# EEPROM_FLASH.net
KiCad netlist of a schematic drawn in Altium Designer
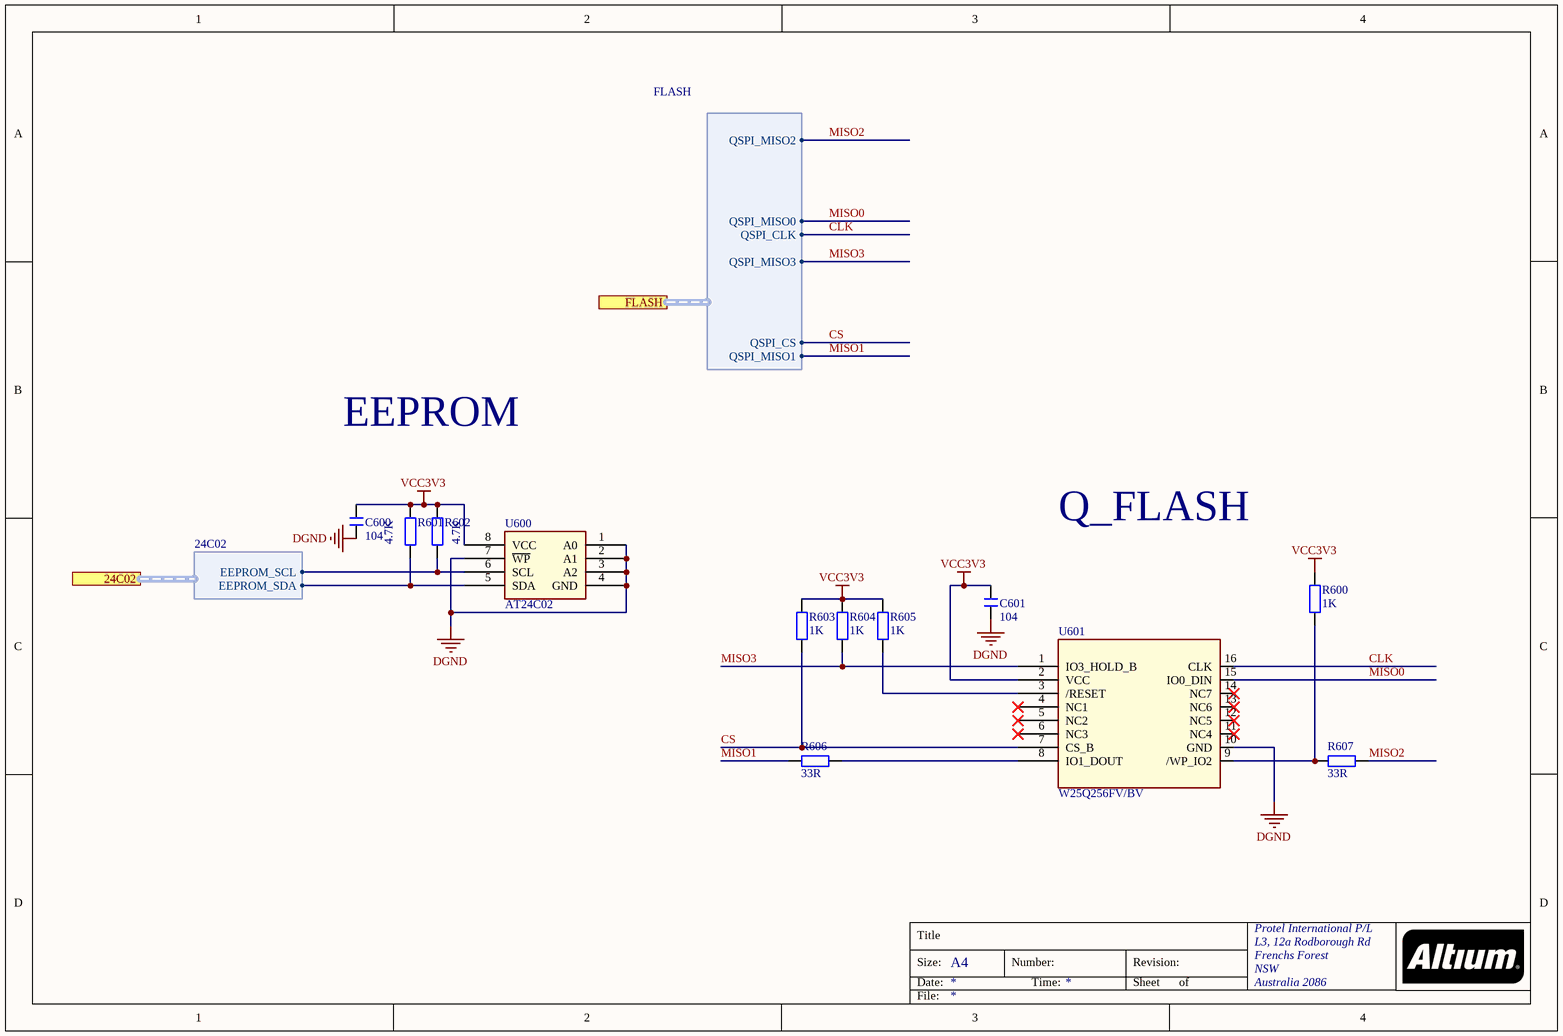
[diagram p0: EEPROM_FLASH.SchDoc]

(export (version "E")
  (design (tool "Eeschema 10.0.6"))
  (components
    (comp (ref "C600")
      (value "104")
      (footprint "C 0402_M")
      (description "无极性贴片电容")
      (fields (field (name "版权归属") "源创客"))
      (libsource (lib "3.1   - 电阻-电容-电感") (part "C"))
    )
    (comp (ref "C601")
      (value "104")
      (footprint "C 0402_M")
      (description "无极性贴片电容")
      (fields (field (name "版权归属") "源创客"))
      (libsource (lib "3.1   - 电阻-电容-电感") (part "C"))
    )
    (comp (ref "R600")
      (value "1K")
      (footprint "R 0402_M")
      (description "贴片电阻")
      (fields (field (name "版权归属") "源创客"))
      (libsource (lib "3.1   - 电阻-电容-电感") (part "R"))
    )
    (comp (ref "R601")
      (value "4.7K")
      (footprint "R 0402_M")
      (description "贴片电阻")
      (fields (field (name "版权归属") "源创客"))
      (libsource (lib "3.1   - 电阻-电容-电感") (part "R"))
    )
    (comp (ref "R602")
      (value "4.7K")
      (footprint "R 0402_M")
      (description "贴片电阻")
      (fields (field (name "版权归属") "源创客"))
      (libsource (lib "3.1   - 电阻-电容-电感") (part "R"))
    )
    (comp (ref "R603")
      (value "1K")
      (footprint "R 0402_M")
      (description "贴片电阻")
      (fields (field (name "版权归属") "源创客"))
      (libsource (lib "3.1   - 电阻-电容-电感") (part "R"))
    )
    (comp (ref "R604")
      (value "1K")
      (footprint "R 0402_M")
      (description "贴片电阻")
      (fields (field (name "版权归属") "源创客"))
      (libsource (lib "3.1   - 电阻-电容-电感") (part "R"))
    )
    (comp (ref "R605")
      (value "1K")
      (footprint "R 0402_M")
      (description "贴片电阻")
      (fields (field (name "版权归属") "源创客"))
      (libsource (lib "3.1   - 电阻-电容-电感") (part "R"))
    )
    (comp (ref "R606")
      (value "33R")
      (footprint "R 0402_M")
      (description "贴片电阻")
      (fields (field (name "版权归属") "源创客"))
      (libsource (lib "3.1   - 电阻-电容-电感") (part "R"))
    )
    (comp (ref "R607")
      (value "33R")
      (footprint "R 0402_M")
      (description "贴片电阻")
      (fields (field (name "版权归属") "源创客"))
      (libsource (lib "3.1   - 电阻-电容-电感") (part "R"))
    )
    (comp (ref "U600")
      (value "AT24C02")
      (footprint "SOP8_M")
      (libsource (lib "altium-import") (part "root_0_mirrored_AT24C02_"))
    )
    (comp (ref "U601")
      (value "W25Q256FV/BV")
      (footprint "SOP16W_M")
      (libsource (lib "altium-import") (part "root_0_W25Q256FV/BV_"))
    )
  )
  (nets
    (net (code "3") (name "/CLK") (class "Default")
      (node (ref "U601") (pin "16") (pinfunction "CLK_16") (pintype "passive"))
    )
    (net (code "4") (name "/CS") (class "Default")
      (node (ref "R603") (pin "1") (pinfunction "1_1") (pintype "passive"))
      (node (ref "U601") (pin "7") (pinfunction "CS_B_7") (pintype "passive"))
    )
    (net (code "5") (name "/MISO0") (class "Default")
      (node (ref "U601") (pin "15") (pinfunction "IO0_DIN_15") (pintype "passive"))
    )
    (net (code "6") (name "/MISO1") (class "Default")
      (node (ref "R606") (pin "2") (pinfunction "2_2") (pintype "passive"))
    )
    (net (code "7") (name "/MISO2") (class "Default")
      (node (ref "R607") (pin "2") (pinfunction "2_2") (pintype "passive"))
    )
    (net (code "8") (name "/MISO3") (class "Default")
      (node (ref "R604") (pin "1") (pinfunction "1_1") (pintype "passive"))
      (node (ref "U601") (pin "1") (pinfunction "IO3_HOLD_B_1") (pintype "passive"))
    )
    (net (code "11") (name "DGND") (class "Default")
      (node (ref "C600") (pin "1") (pinfunction "1_1") (pintype "passive"))
      (node (ref "C601") (pin "1") (pinfunction "1_1") (pintype "passive"))
      (node (ref "U600") (pin "1") (pinfunction "A0_1") (pintype "power_in"))
      (node (ref "U600") (pin "2") (pinfunction "A1_2") (pintype "power_in"))
      (node (ref "U600") (pin "3") (pinfunction "A2_3") (pintype "power_in"))
      (node (ref "U600") (pin "4") (pinfunction "GND_4") (pintype "passive"))
      (node (ref "U600") (pin "7") (pinfunction "~{WP}_7") (pintype "passive"))
      (node (ref "U601") (pin "10") (pinfunction "GND_10") (pintype "passive"))
    )
    (net (code "12") (name "Net-(U600-SCL)") (class "Default")
      (node (ref "R602") (pin "1") (pinfunction "1_1") (pintype "passive"))
      (node (ref "U600") (pin "6") (pinfunction "SCL_6") (pintype "passive"))
    )
    (net (code "13") (name "Net-(U600-SDA)") (class "Default")
      (node (ref "R601") (pin "1") (pinfunction "1_1") (pintype "passive"))
      (node (ref "U600") (pin "5") (pinfunction "SDA_5") (pintype "passive"))
    )
    (net (code "14") (name "Net-(U601-IO1_DOUT)") (class "Default")
      (node (ref "R606") (pin "1") (pinfunction "1_1") (pintype "passive"))
      (node (ref "U601") (pin "8") (pinfunction "IO1_DOUT_8") (pintype "passive"))
    )
    (net (code "15") (name "Net-(U601-{slash}RESET)") (class "Default")
      (node (ref "R605") (pin "1") (pinfunction "1_1") (pintype "passive"))
      (node (ref "U601") (pin "3") (pinfunction "/RESET_3") (pintype "passive"))
    )
    (net (code "16") (name "Net-(U601-{slash}WP_IO2)") (class "Default")
      (node (ref "R600") (pin "1") (pinfunction "1_1") (pintype "passive"))
      (node (ref "R607") (pin "1") (pinfunction "1_1") (pintype "passive"))
      (node (ref "U601") (pin "9") (pinfunction "/WP_IO2_9") (pintype "passive"))
    )
    (net (code "17") (name "VCC3V3") (class "Default")
      (node (ref "C600") (pin "2") (pinfunction "2_2") (pintype "passive"))
      (node (ref "C601") (pin "2") (pinfunction "2_2") (pintype "passive"))
      (node (ref "R600") (pin "2") (pinfunction "2_2") (pintype "passive"))
      (node (ref "R601") (pin "2") (pinfunction "2_2") (pintype "passive"))
      (node (ref "R602") (pin "2") (pinfunction "2_2") (pintype "passive"))
      (node (ref "R603") (pin "2") (pinfunction "2_2") (pintype "passive"))
      (node (ref "R604") (pin "2") (pinfunction "2_2") (pintype "passive"))
      (node (ref "R605") (pin "2") (pinfunction "2_2") (pintype "passive"))
      (node (ref "U600") (pin "8") (pinfunction "VCC_8") (pintype "passive"))
      (node (ref "U601") (pin "2") (pinfunction "VCC_2") (pintype "passive"))
    )
    (net (code "18") (name "unconnected-(U601-NC1-Pad4)") (class "Default")
      (node (ref "U601") (pin "4") (pinfunction "NC1_4") (pintype "passive+no_connect"))
    )
    (net (code "19") (name "unconnected-(U601-NC2-Pad5)") (class "Default")
      (node (ref "U601") (pin "5") (pinfunction "NC2_5") (pintype "passive+no_connect"))
    )
    (net (code "20") (name "unconnected-(U601-NC3-Pad6)") (class "Default")
      (node (ref "U601") (pin "6") (pinfunction "NC3_6") (pintype "passive+no_connect"))
    )
    (net (code "21") (name "unconnected-(U601-NC4-Pad11)") (class "Default")
      (node (ref "U601") (pin "11") (pinfunction "NC4_11") (pintype "passive+no_connect"))
    )
    (net (code "22") (name "unconnected-(U601-NC5-Pad12)") (class "Default")
      (node (ref "U601") (pin "12") (pinfunction "NC5_12") (pintype "passive+no_connect"))
    )
    (net (code "23") (name "unconnected-(U601-NC6-Pad13)") (class "Default")
      (node (ref "U601") (pin "13") (pinfunction "NC6_13") (pintype "passive+no_connect"))
    )
    (net (code "24") (name "unconnected-(U601-NC7-Pad14)") (class "Default")
      (node (ref "U601") (pin "14") (pinfunction "NC7_14") (pintype "passive+no_connect"))
    )
  )
)
